# STM32F4_MCU.net
KiCad netlist of a schematic drawn in Altium Designer
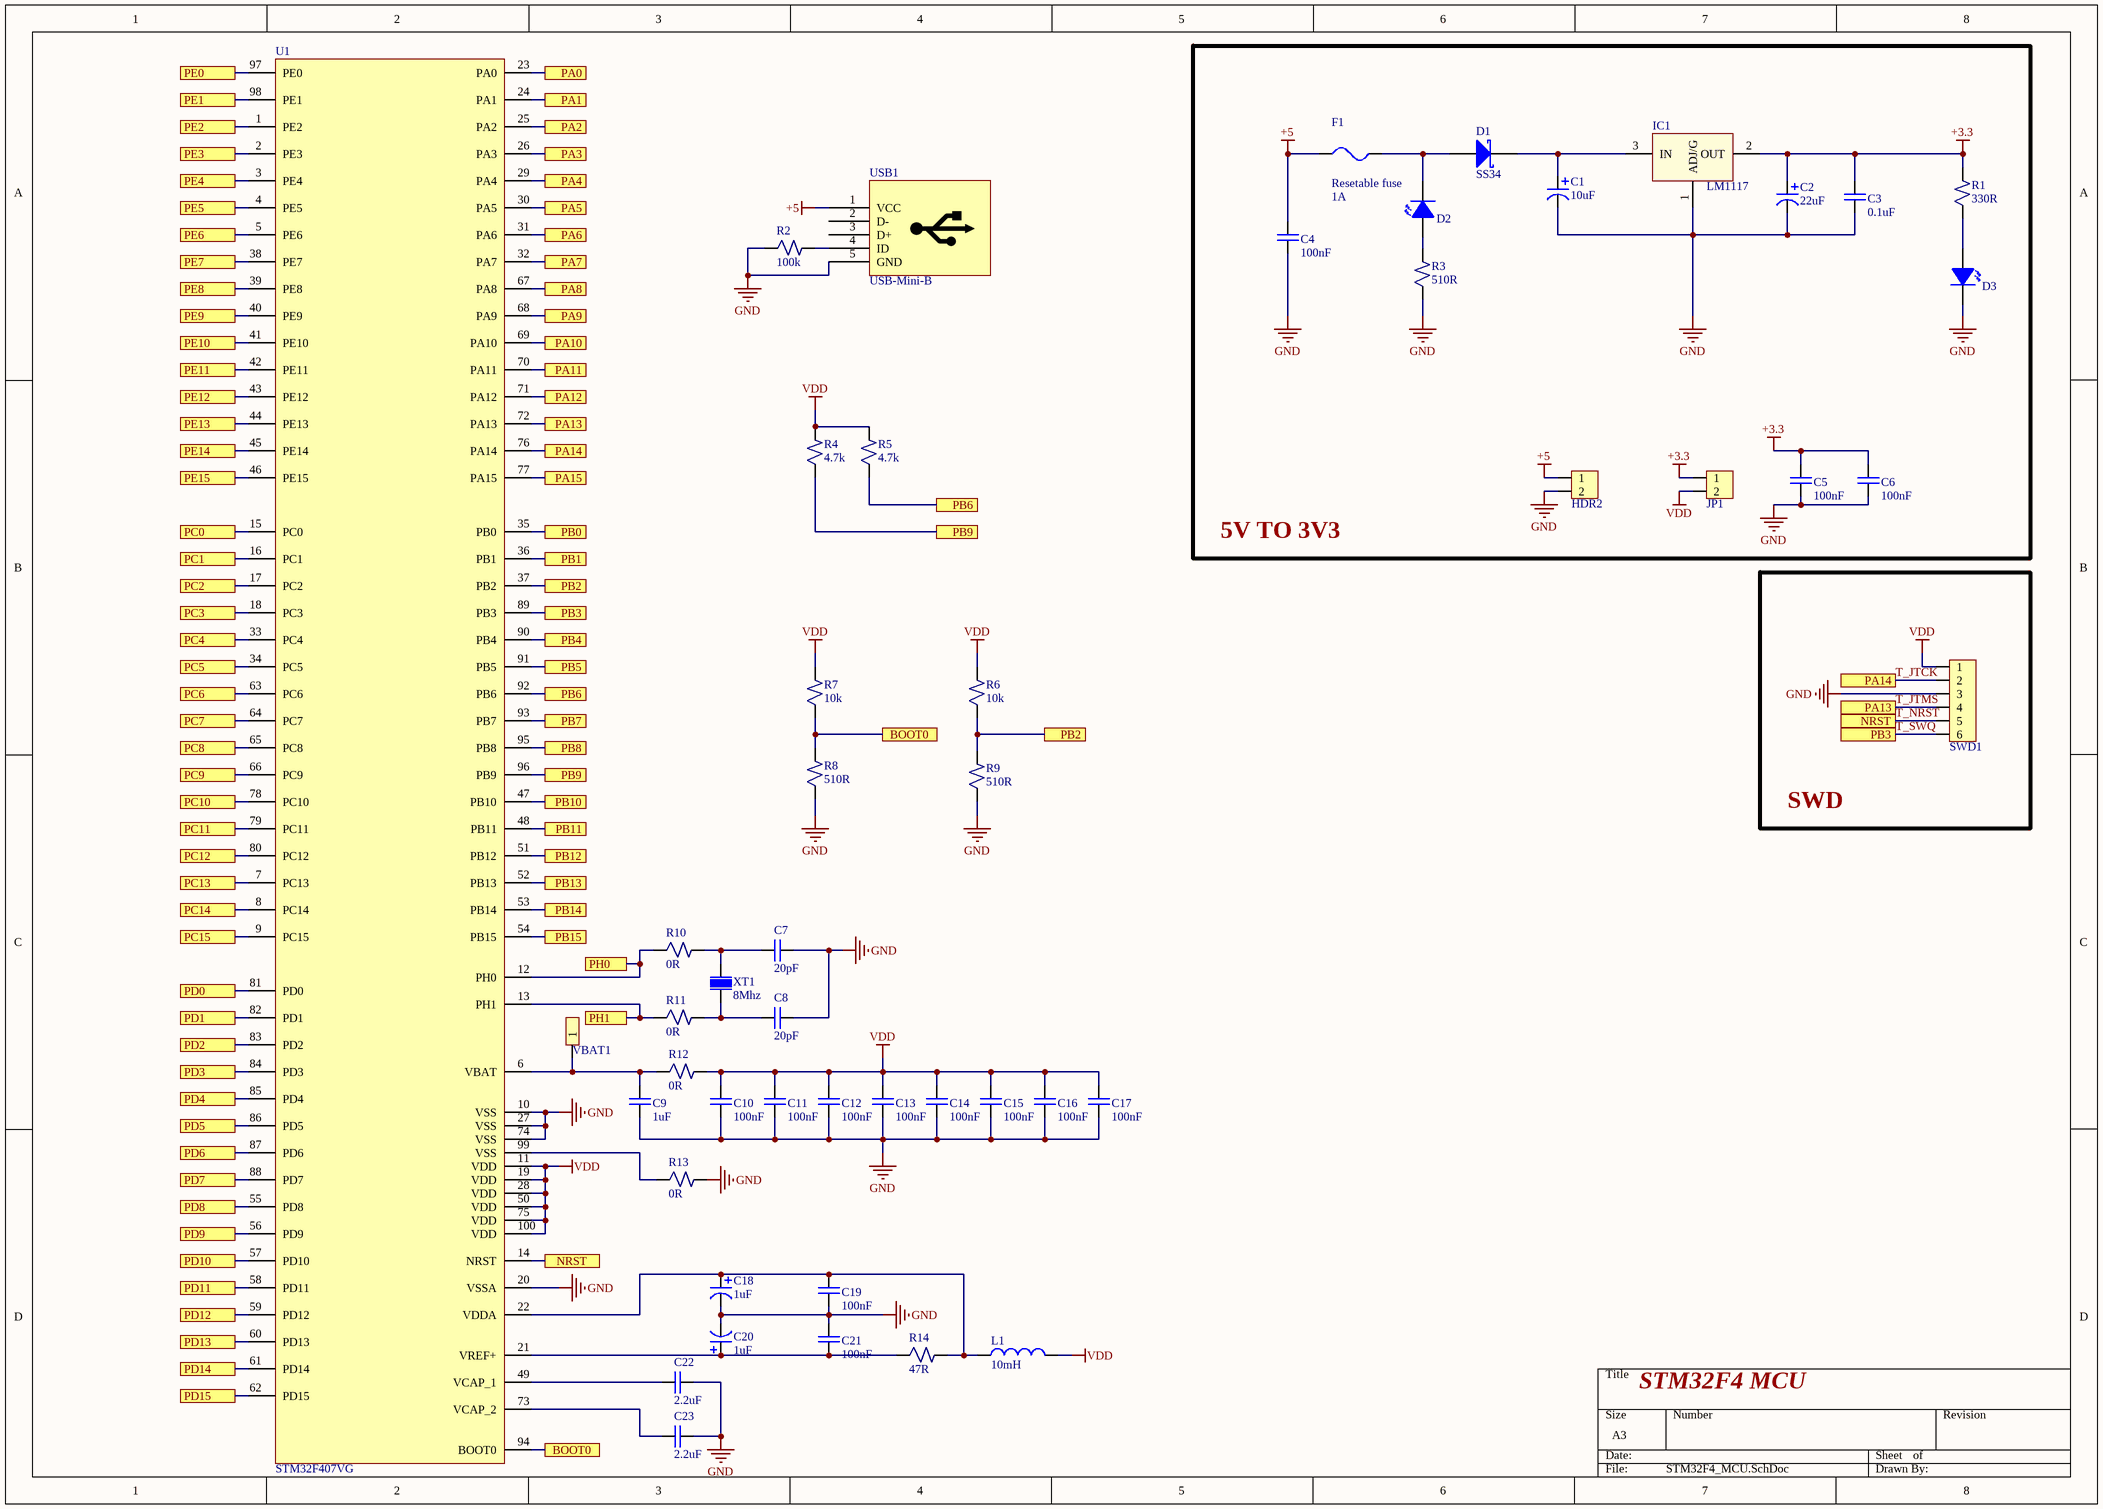
[diagram p0: STM32F4_MCU.SchDoc]

(export (version "E")
  (design (tool "Eeschema 10.0.6"))
  (components
    (comp (ref "C1")
      (value "10uF")
      (footprint "C3216-Tantalum")
      (description "Polarized Capacitor")
      (fields (field (name "Comment") "Cap Tantalum"))
      (libsource (lib "STM32F4_Board") (part "Cap Pol_2"))
    )
    (comp (ref "C2")
      (value "22uF")
      (footprint "C3216-Tantalum")
      (description "Polarized Capacitor")
      (fields (field (name "Comment") "Cap Pol"))
      (libsource (lib "STM32F4_Board") (part "Cap Pol_1"))
    )
    (comp (ref "C3")
      (value "0.1uF")
      (footprint "C0805")
      (description "Non-Polarized Capacitor")
      (fields (field (name "Comment") "Cap Non-Pol"))
      (libsource (lib "STM32F4_Board") (part "Cap Non-Pol_4"))
    )
    (comp (ref "C4")
      (value "100nF")
      (footprint "C0805")
      (description "Non-Polarized Capacitor")
      (fields (field (name "Comment") "Cap Non-Pol"))
      (libsource (lib "STM32F4_Board") (part "Cap Non-Pol"))
    )
    (comp (ref "C5")
      (value "100nF")
      (footprint "C0805")
      (description "Non-Polarized Capacitor")
      (fields (field (name "Comment") "Cap Non-Pol"))
      (libsource (lib "STM32F4_Board") (part "Cap Non-Pol"))
    )
    (comp (ref "C6")
      (value "100nF")
      (footprint "C0805")
      (description "Non-Polarized Capacitor")
      (fields (field (name "Comment") "Cap Non-Pol"))
      (libsource (lib "STM32F4_Board") (part "Cap Non-Pol"))
    )
    (comp (ref "C7")
      (value "20pF")
      (footprint "C0805")
      (description "Non-Polarized Capacitor")
      (fields (field (name "Comment") "Cap Non-Pol"))
      (libsource (lib "STM32F4_Board") (part "Cap Non-Pol_3"))
    )
    (comp (ref "C8")
      (value "20pF")
      (footprint "C0805")
      (description "Non-Polarized Capacitor")
      (fields (field (name "Comment") "Cap Non-Pol"))
      (libsource (lib "STM32F4_Board") (part "Cap Non-Pol_3"))
    )
    (comp (ref "C9")
      (value "1uF")
      (footprint "C0805")
      (description "Non-Polarized Capacitor")
      (fields (field (name "Comment") "Cap Non-Pol"))
      (libsource (lib "STM32F4_Board") (part "Cap Non-Pol_1"))
    )
    (comp (ref "C10")
      (value "100nF")
      (footprint "C0805")
      (description "Non-Polarized Capacitor")
      (fields (field (name "Comment") "Cap Non-Pol"))
      (libsource (lib "STM32F4_Board") (part "Cap Non-Pol"))
    )
    (comp (ref "C11")
      (value "100nF")
      (footprint "C0805")
      (description "Non-Polarized Capacitor")
      (fields (field (name "Comment") "Cap Non-Pol"))
      (libsource (lib "STM32F4_Board") (part "Cap Non-Pol"))
    )
    (comp (ref "C12")
      (value "100nF")
      (footprint "C0805")
      (description "Non-Polarized Capacitor")
      (fields (field (name "Comment") "Cap Non-Pol"))
      (libsource (lib "STM32F4_Board") (part "Cap Non-Pol"))
    )
    (comp (ref "C13")
      (value "100nF")
      (footprint "C0805")
      (description "Non-Polarized Capacitor")
      (fields (field (name "Comment") "Cap Non-Pol"))
      (libsource (lib "STM32F4_Board") (part "Cap Non-Pol"))
    )
    (comp (ref "C14")
      (value "100nF")
      (footprint "C0805")
      (description "Non-Polarized Capacitor")
      (fields (field (name "Comment") "Cap Non-Pol"))
      (libsource (lib "STM32F4_Board") (part "Cap Non-Pol"))
    )
    (comp (ref "C15")
      (value "100nF")
      (footprint "C0805")
      (description "Non-Polarized Capacitor")
      (fields (field (name "Comment") "Cap Non-Pol"))
      (libsource (lib "STM32F4_Board") (part "Cap Non-Pol"))
    )
    (comp (ref "C16")
      (value "100nF")
      (footprint "C0805")
      (description "Non-Polarized Capacitor")
      (fields (field (name "Comment") "Cap Non-Pol"))
      (libsource (lib "STM32F4_Board") (part "Cap Non-Pol"))
    )
    (comp (ref "C17")
      (value "100nF")
      (footprint "C0805")
      (description "Non-Polarized Capacitor")
      (fields (field (name "Comment") "Cap Non-Pol"))
      (libsource (lib "STM32F4_Board") (part "Cap Non-Pol"))
    )
    (comp (ref "C18")
      (value "1uF")
      (footprint "C3216-Tantalum")
      (description "Polarized Capacitor")
      (fields (field (name "Comment") "Cap Pol"))
      (libsource (lib "STM32F4_Board") (part "Cap Pol"))
    )
    (comp (ref "C19")
      (value "100nF")
      (footprint "C0805")
      (description "Non-Polarized Capacitor")
      (fields (field (name "Comment") "Cap Non-Pol"))
      (libsource (lib "STM32F4_Board") (part "Cap Non-Pol"))
    )
    (comp (ref "C20")
      (value "1uF")
      (footprint "C3216-Tantalum")
      (description "Polarized Capacitor")
      (fields (field (name "Comment") "Cap Pol"))
      (libsource (lib "STM32F4_Board") (part "Cap Pol"))
    )
    (comp (ref "C21")
      (value "100nF")
      (footprint "C0805")
      (description "Non-Polarized Capacitor")
      (fields (field (name "Comment") "Cap Non-Pol"))
      (libsource (lib "STM32F4_Board") (part "Cap Non-Pol"))
    )
    (comp (ref "C22")
      (value "2.2uF")
      (footprint "C0805")
      (description "Non-Polarized Capacitor")
      (fields (field (name "Comment") "Cap Non-Pol"))
      (libsource (lib "STM32F4_Board") (part "Cap Non-Pol_2"))
    )
    (comp (ref "C23")
      (value "2.2uF")
      (footprint "C0805")
      (description "Non-Polarized Capacitor")
      (fields (field (name "Comment") "Cap Non-Pol"))
      (libsource (lib "STM32F4_Board") (part "Cap Non-Pol_2"))
    )
    (comp (ref "D1")
      (value "SS34")
      (footprint "SMA")
      (description "Schottky Diode")
      (fields (field (name "PUBLISHER") "Altium Limited"))
      (libsource (lib "STM32F4_Board") (part "Diode Schottky"))
    )
    (comp (ref "D2") (value "LED") (footprint "LED0805") (libsource (lib "STM32F4_Board") (part "LED")))
    (comp (ref "D3") (value "LED") (footprint "LED0805") (libsource (lib "STM32F4_Board") (part "LED")))
    (comp (ref "F1")
      (value "Resetable fuse")
      (footprint "FUSE SMD")
      (description "Fuse")
      (fields (field (name "MAXCURRENT") "1A"))
      (libsource (lib "STM32F4_Board") (part "Fuse"))
    )
    (comp (ref "HDR2")
      (value "Header-2")
      (footprint "Header-2")
      (description "Header 2 pins")
      (libsource (lib "STM32F4_Board") (part "Header-2"))
    )
    (comp (ref "IC1")
      (value "LM1117")
      (footprint "SOT-223/SC-73")
      (description "Available in 1.8V, 2.5V, 2.85V, 3.3V, 5V, and  Adjustable Versions")
      (libsource (lib "STM32F4_Board") (part "LM1117"))
    )
    (comp (ref "JP1")
      (value "Header-2")
      (footprint "Header-2")
      (description "Header 2 pins")
      (libsource (lib "STM32F4_Board") (part "Header-2"))
    )
    (comp (ref "L1")
      (value "10mH")
      (footprint "R0805")
      (description "Inductor")
      (libsource (lib "STM32F4_Board") (part "Inductor"))
    )
    (comp (ref "R1")
      (value "330R")
      (footprint "R0805")
      (description "Resistor")
      (libsource (lib "STM32F4_Board") (part "Resistor_5"))
    )
    (comp (ref "R2")
      (value "100k")
      (footprint "R0805")
      (description "Resistor")
      (libsource (lib "STM32F4_Board") (part "Resistor_6"))
    )
    (comp (ref "R3")
      (value "510R")
      (footprint "R0805")
      (description "Resistor")
      (libsource (lib "STM32F4_Board") (part "Resistor_3"))
    )
    (comp (ref "R4")
      (value "4.7k")
      (footprint "R0805")
      (description "Resistor")
      (libsource (lib "STM32F4_Board") (part "Resistor_4"))
    )
    (comp (ref "R5")
      (value "4.7k")
      (footprint "R0805")
      (description "Resistor")
      (libsource (lib "STM32F4_Board") (part "Resistor_4"))
    )
    (comp (ref "R6")
      (value "10k")
      (footprint "R0805")
      (description "Resistor")
      (libsource (lib "STM32F4_Board") (part "Resistor_2"))
    )
    (comp (ref "R7")
      (value "10k")
      (footprint "R0805")
      (description "Resistor")
      (libsource (lib "STM32F4_Board") (part "Resistor_2"))
    )
    (comp (ref "R8")
      (value "510R")
      (footprint "R0805")
      (description "Resistor")
      (libsource (lib "STM32F4_Board") (part "Resistor_3"))
    )
    (comp (ref "R9")
      (value "510R")
      (footprint "R0805")
      (description "Resistor")
      (libsource (lib "STM32F4_Board") (part "Resistor_3"))
    )
    (comp (ref "R10")
      (value "0R")
      (footprint "R0805")
      (description "Resistor")
      (libsource (lib "STM32F4_Board") (part "Resistor_1"))
    )
    (comp (ref "R11")
      (value "0R")
      (footprint "R0805")
      (description "Resistor")
      (libsource (lib "STM32F4_Board") (part "Resistor_1"))
    )
    (comp (ref "R12")
      (value "0R")
      (footprint "R0805")
      (description "Resistor")
      (libsource (lib "STM32F4_Board") (part "Resistor_1"))
    )
    (comp (ref "R13")
      (value "0R")
      (footprint "R0805")
      (description "Resistor")
      (libsource (lib "STM32F4_Board") (part "Resistor_1"))
    )
    (comp (ref "R14")
      (value "47R")
      (footprint "R0805")
      (description "Resistor")
      (libsource (lib "STM32F4_Board") (part "Resistor"))
    )
    (comp (ref "SWD1")
      (value "Header-6")
      (footprint "Header-6")
      (description "Header 6 pins")
      (libsource (lib "STM32F4_Board") (part "Header-6"))
    )
    (comp (ref "U1")
      (value "STM32F407VG")
      (footprint "LQFP100")
      (libsource (lib "STM32F4_Board") (part "STM32F407VG"))
    )
    (comp (ref "USB1")
      (value "USB-Mini-B")
      (footprint "USB_B_MINI_SMD")
      (libsource (lib "STM32F4_Board") (part "USB-Mini"))
    )
    (comp (ref "VBAT1")
      (value "Header-1")
      (footprint "Header-1")
      (description "Header 1 pin")
      (libsource (lib "STM32F4_Board") (part "Header-1"))
    )
    (comp (ref "XT1")
      (value "XTAL")
      (footprint "XT2")
      (description "Crystal")
      (fields (field (name "FREQUENCY") "8Mhz"))
      (libsource (lib "STM32F4_Board") (part "XTAL"))
    )
  )
  (nets
    (net (code "1") (name "+3.3") (class "Default")
      (node (ref "C2") (pin "1") (pinfunction "1_1") (pintype "passive"))
      (node (ref "C3") (pin "2") (pinfunction "2_2") (pintype "passive"))
      (node (ref "C5") (pin "2") (pinfunction "2_2") (pintype "passive"))
      (node (ref "C6") (pin "2") (pinfunction "2_2") (pintype "passive"))
      (node (ref "IC1") (pin "2") (pinfunction "OUT_2") (pintype "passive"))
      (node (ref "JP1") (pin "1") (pinfunction "1_1") (pintype "passive"))
      (node (ref "R1") (pin "2") (pintype "passive"))
    )
    (net (code "2") (name "+5") (class "Default")
      (node (ref "C4") (pin "2") (pinfunction "2_2") (pintype "passive"))
      (node (ref "F1") (pin "1") (pinfunction "1_1") (pintype "passive"))
      (node (ref "HDR2") (pin "1") (pinfunction "1_1") (pintype "passive"))
      (node (ref "USB1") (pin "1") (pinfunction "VCC_1") (pintype "passive"))
    )
    (net (code "3") (name "/BOOT0") (class "Default")
      (node (ref "R7") (pin "1") (pintype "passive"))
      (node (ref "R8") (pin "2") (pintype "passive"))
      (node (ref "U1") (pin "94") (pinfunction "BOOT0_94") (pintype "passive"))
    )
    (net (code "4") (name "/PA0") (class "Default")
      (node (ref "U1") (pin "23") (pinfunction "PA0_23") (pintype "passive"))
    )
    (net (code "5") (name "/PA1") (class "Default")
      (node (ref "U1") (pin "24") (pinfunction "PA1_24") (pintype "passive"))
    )
    (net (code "6") (name "/PA2") (class "Default")
      (node (ref "U1") (pin "25") (pinfunction "PA2_25") (pintype "passive"))
    )
    (net (code "7") (name "/PA3") (class "Default")
      (node (ref "U1") (pin "26") (pinfunction "PA3_26") (pintype "passive"))
    )
    (net (code "8") (name "/PA4") (class "Default")
      (node (ref "U1") (pin "29") (pinfunction "PA4_29") (pintype "passive"))
    )
    (net (code "9") (name "/PA5") (class "Default")
      (node (ref "U1") (pin "30") (pinfunction "PA5_30") (pintype "passive"))
    )
    (net (code "10") (name "/PA6") (class "Default")
      (node (ref "U1") (pin "31") (pinfunction "PA6_31") (pintype "passive"))
    )
    (net (code "11") (name "/PA7") (class "Default")
      (node (ref "U1") (pin "32") (pinfunction "PA7_32") (pintype "passive"))
    )
    (net (code "12") (name "/PA8") (class "Default")
      (node (ref "U1") (pin "67") (pinfunction "PA8_67") (pintype "passive"))
    )
    (net (code "13") (name "/PA9") (class "Default")
      (node (ref "U1") (pin "68") (pinfunction "PA9_68") (pintype "passive"))
    )
    (net (code "14") (name "/PA10") (class "Default")
      (node (ref "U1") (pin "69") (pinfunction "PA10_69") (pintype "passive"))
    )
    (net (code "15") (name "/PA11") (class "Default")
      (node (ref "U1") (pin "70") (pinfunction "PA11_70") (pintype "passive"))
    )
    (net (code "16") (name "/PA12") (class "Default")
      (node (ref "U1") (pin "71") (pinfunction "PA12_71") (pintype "passive"))
    )
    (net (code "17") (name "/PA15") (class "Default")
      (node (ref "U1") (pin "77") (pinfunction "PA15_77") (pintype "passive"))
    )
    (net (code "18") (name "/PB0") (class "Default")
      (node (ref "U1") (pin "35") (pinfunction "PB0_35") (pintype "passive"))
    )
    (net (code "19") (name "/PB1") (class "Default")
      (node (ref "U1") (pin "36") (pinfunction "PB1_36") (pintype "passive"))
    )
    (net (code "20") (name "/PB2") (class "Default")
      (node (ref "R6") (pin "1") (pintype "passive"))
      (node (ref "R9") (pin "2") (pintype "passive"))
      (node (ref "U1") (pin "37") (pinfunction "PB2_37") (pintype "passive"))
    )
    (net (code "21") (name "/PB4") (class "Default")
      (node (ref "U1") (pin "90") (pinfunction "PB4_90") (pintype "passive"))
    )
    (net (code "22") (name "/PB5") (class "Default")
      (node (ref "U1") (pin "91") (pinfunction "PB5_91") (pintype "passive"))
    )
    (net (code "23") (name "/PB6") (class "Default")
      (node (ref "R5") (pin "1") (pintype "passive"))
      (node (ref "U1") (pin "92") (pinfunction "PB6_92") (pintype "passive"))
    )
    (net (code "24") (name "/PB7") (class "Default")
      (node (ref "U1") (pin "93") (pinfunction "PB7_93") (pintype "passive"))
    )
    (net (code "25") (name "/PB8") (class "Default")
      (node (ref "U1") (pin "95") (pinfunction "PB8_95") (pintype "passive"))
    )
    (net (code "26") (name "/PB9") (class "Default")
      (node (ref "R4") (pin "1") (pintype "passive"))
      (node (ref "U1") (pin "96") (pinfunction "PB9_96") (pintype "passive"))
    )
    (net (code "27") (name "/PB10") (class "Default")
      (node (ref "U1") (pin "47") (pinfunction "PB10_47") (pintype "passive"))
    )
    (net (code "28") (name "/PB11") (class "Default")
      (node (ref "U1") (pin "48") (pinfunction "PB11_48") (pintype "passive"))
    )
    (net (code "29") (name "/PB12") (class "Default")
      (node (ref "U1") (pin "51") (pinfunction "PB12_51") (pintype "passive"))
    )
    (net (code "30") (name "/PB13") (class "Default")
      (node (ref "U1") (pin "52") (pinfunction "PB13_52") (pintype "passive"))
    )
    (net (code "31") (name "/PB14") (class "Default")
      (node (ref "U1") (pin "53") (pinfunction "PB14_53") (pintype "passive"))
    )
    (net (code "32") (name "/PB15") (class "Default")
      (node (ref "U1") (pin "54") (pinfunction "PB15_54") (pintype "passive"))
    )
    (net (code "33") (name "/PC0") (class "Default")
      (node (ref "U1") (pin "15") (pinfunction "PC0_15") (pintype "passive"))
    )
    (net (code "34") (name "/PC1") (class "Default")
      (node (ref "U1") (pin "16") (pinfunction "PC1_16") (pintype "passive"))
    )
    (net (code "35") (name "/PC2") (class "Default")
      (node (ref "U1") (pin "17") (pinfunction "PC2_17") (pintype "passive"))
    )
    (net (code "36") (name "/PC3") (class "Default")
      (node (ref "U1") (pin "18") (pinfunction "PC3_18") (pintype "passive"))
    )
    (net (code "37") (name "/PC4") (class "Default")
      (node (ref "U1") (pin "33") (pinfunction "PC4_33") (pintype "passive"))
    )
    (net (code "38") (name "/PC5") (class "Default")
      (node (ref "U1") (pin "34") (pinfunction "PC5_34") (pintype "passive"))
    )
    (net (code "39") (name "/PC6") (class "Default")
      (node (ref "U1") (pin "63") (pinfunction "PC6_63") (pintype "passive"))
    )
    (net (code "40") (name "/PC7") (class "Default")
      (node (ref "U1") (pin "64") (pinfunction "PC7_64") (pintype "passive"))
    )
    (net (code "41") (name "/PC8") (class "Default")
      (node (ref "U1") (pin "65") (pinfunction "PC8_65") (pintype "passive"))
    )
    (net (code "42") (name "/PC9") (class "Default")
      (node (ref "U1") (pin "66") (pinfunction "PC9_66") (pintype "passive"))
    )
    (net (code "43") (name "/PC10") (class "Default")
      (node (ref "U1") (pin "78") (pinfunction "PC10_78") (pintype "passive"))
    )
    (net (code "44") (name "/PC11") (class "Default")
      (node (ref "U1") (pin "79") (pinfunction "PC11_79") (pintype "passive"))
    )
    (net (code "45") (name "/PC12") (class "Default")
      (node (ref "U1") (pin "80") (pinfunction "PC12_80") (pintype "passive"))
    )
    (net (code "46") (name "/PC13") (class "Default")
      (node (ref "U1") (pin "7") (pinfunction "PC13_7") (pintype "passive"))
    )
    (net (code "47") (name "/PC14") (class "Default")
      (node (ref "U1") (pin "8") (pinfunction "PC14_8") (pintype "passive"))
    )
    (net (code "48") (name "/PC15") (class "Default")
      (node (ref "U1") (pin "9") (pinfunction "PC15_9") (pintype "passive"))
    )
    (net (code "49") (name "/PD0") (class "Default")
      (node (ref "U1") (pin "81") (pinfunction "PD0_81") (pintype "passive"))
    )
    (net (code "50") (name "/PD1") (class "Default")
      (node (ref "U1") (pin "82") (pinfunction "PD1_82") (pintype "passive"))
    )
    (net (code "51") (name "/PD2") (class "Default")
      (node (ref "U1") (pin "83") (pinfunction "PD2_83") (pintype "passive"))
    )
    (net (code "52") (name "/PD3") (class "Default")
      (node (ref "U1") (pin "84") (pinfunction "PD3_84") (pintype "passive"))
    )
    (net (code "53") (name "/PD4") (class "Default")
      (node (ref "U1") (pin "85") (pinfunction "PD4_85") (pintype "passive"))
    )
    (net (code "54") (name "/PD5") (class "Default")
      (node (ref "U1") (pin "86") (pinfunction "PD5_86") (pintype "passive"))
    )
    (net (code "55") (name "/PD6") (class "Default")
      (node (ref "U1") (pin "87") (pinfunction "PD6_87") (pintype "passive"))
    )
    (net (code "56") (name "/PD7") (class "Default")
      (node (ref "U1") (pin "88") (pinfunction "PD7_88") (pintype "passive"))
    )
    (net (code "57") (name "/PD8") (class "Default")
      (node (ref "U1") (pin "55") (pinfunction "PD8_55") (pintype "passive"))
    )
    (net (code "58") (name "/PD9") (class "Default")
      (node (ref "U1") (pin "56") (pinfunction "PD9_56") (pintype "passive"))
    )
    (net (code "59") (name "/PD10") (class "Default")
      (node (ref "U1") (pin "57") (pinfunction "PD10_57") (pintype "passive"))
    )
    (net (code "60") (name "/PD11") (class "Default")
      (node (ref "U1") (pin "58") (pinfunction "PD11_58") (pintype "passive"))
    )
    (net (code "61") (name "/PD12") (class "Default")
      (node (ref "U1") (pin "59") (pinfunction "PD12_59") (pintype "passive"))
    )
    (net (code "62") (name "/PD13") (class "Default")
      (node (ref "U1") (pin "60") (pinfunction "PD13_60") (pintype "passive"))
    )
    (net (code "63") (name "/PD14") (class "Default")
      (node (ref "U1") (pin "61") (pinfunction "PD14_61") (pintype "passive"))
    )
    (net (code "64") (name "/PD15") (class "Default")
      (node (ref "U1") (pin "62") (pinfunction "PD15_62") (pintype "passive"))
    )
    (net (code "65") (name "/PE0") (class "Default")
      (node (ref "U1") (pin "97") (pinfunction "PE0_97") (pintype "passive"))
    )
    (net (code "66") (name "/PE1") (class "Default")
      (node (ref "U1") (pin "98") (pinfunction "PE1_98") (pintype "passive"))
    )
    (net (code "67") (name "/PE2") (class "Default")
      (node (ref "U1") (pin "1") (pinfunction "PE2_1") (pintype "passive"))
    )
    (net (code "68") (name "/PE3") (class "Default")
      (node (ref "U1") (pin "2") (pinfunction "PE3_2") (pintype "passive"))
    )
    (net (code "69") (name "/PE4") (class "Default")
      (node (ref "U1") (pin "3") (pinfunction "PE4_3") (pintype "passive"))
    )
    (net (code "70") (name "/PE5") (class "Default")
      (node (ref "U1") (pin "4") (pinfunction "PE5_4") (pintype "passive"))
    )
    (net (code "71") (name "/PE6") (class "Default")
      (node (ref "U1") (pin "5") (pinfunction "PE6_5") (pintype "passive"))
    )
    (net (code "72") (name "/PE7") (class "Default")
      (node (ref "U1") (pin "38") (pinfunction "PE7_38") (pintype "passive"))
    )
    (net (code "73") (name "/PE8") (class "Default")
      (node (ref "U1") (pin "39") (pinfunction "PE8_39") (pintype "passive"))
    )
    (net (code "74") (name "/PE9") (class "Default")
      (node (ref "U1") (pin "40") (pinfunction "PE9_40") (pintype "passive"))
    )
    (net (code "75") (name "/PE10") (class "Default")
      (node (ref "U1") (pin "41") (pinfunction "PE10_41") (pintype "passive"))
    )
    (net (code "76") (name "/PE11") (class "Default")
      (node (ref "U1") (pin "42") (pinfunction "PE11_42") (pintype "passive"))
    )
    (net (code "77") (name "/PE12") (class "Default")
      (node (ref "U1") (pin "43") (pinfunction "PE12_43") (pintype "passive"))
    )
    (net (code "78") (name "/PE13") (class "Default")
      (node (ref "U1") (pin "44") (pinfunction "PE13_44") (pintype "passive"))
    )
    (net (code "79") (name "/PE14") (class "Default")
      (node (ref "U1") (pin "45") (pinfunction "PE14_45") (pintype "passive"))
    )
    (net (code "80") (name "/PE15") (class "Default")
      (node (ref "U1") (pin "46") (pinfunction "PE15_46") (pintype "passive"))
    )
    (net (code "81") (name "/PH0") (class "Default")
      (node (ref "R10") (pin "1") (pintype "passive"))
      (node (ref "U1") (pin "12") (pinfunction "PH0_12") (pintype "passive"))
    )
    (net (code "82") (name "/PH1") (class "Default")
      (node (ref "R11") (pin "1") (pintype "passive"))
      (node (ref "U1") (pin "13") (pinfunction "PH1_13") (pintype "passive"))
    )
    (net (code "83") (name "/T_JTCK") (class "Default")
      (node (ref "SWD1") (pin "2") (pinfunction "2_2") (pintype "passive"))
      (node (ref "U1") (pin "76") (pinfunction "PA14_76") (pintype "passive"))
    )
    (net (code "84") (name "/T_JTMS") (class "Default")
      (node (ref "SWD1") (pin "4") (pinfunction "4_4") (pintype "passive"))
      (node (ref "U1") (pin "72") (pinfunction "PA13_72") (pintype "passive"))
    )
    (net (code "85") (name "/T_NRST") (class "Default")
      (node (ref "SWD1") (pin "5") (pinfunction "5_5") (pintype "passive"))
      (node (ref "U1") (pin "14") (pinfunction "NRST_14") (pintype "passive"))
    )
    (net (code "86") (name "/T_SWQ") (class "Default")
      (node (ref "SWD1") (pin "6") (pinfunction "6_6") (pintype "passive"))
      (node (ref "U1") (pin "89") (pinfunction "PB3_89") (pintype "passive"))
    )
    (net (code "87") (name "GND") (class "Default")
      (node (ref "C1") (pin "2") (pinfunction "2_2") (pintype "passive"))
      (node (ref "C10") (pin "2") (pinfunction "2_2") (pintype "passive"))
      (node (ref "C11") (pin "2") (pinfunction "2_2") (pintype "passive"))
      (node (ref "C12") (pin "2") (pinfunction "2_2") (pintype "passive"))
      (node (ref "C13") (pin "2") (pinfunction "2_2") (pintype "passive"))
      (node (ref "C14") (pin "2") (pinfunction "2_2") (pintype "passive"))
      (node (ref "C15") (pin "2") (pinfunction "2_2") (pintype "passive"))
      (node (ref "C16") (pin "2") (pinfunction "2_2") (pintype "passive"))
      (node (ref "C17") (pin "2") (pinfunction "2_2") (pintype "passive"))
      (node (ref "C18") (pin "2") (pinfunction "2_2") (pintype "passive"))
      (node (ref "C19") (pin "1") (pinfunction "1_1") (pintype "passive"))
      (node (ref "C2") (pin "2") (pinfunction "2_2") (pintype "passive"))
      (node (ref "C20") (pin "2") (pinfunction "2_2") (pintype "passive"))
      (node (ref "C21") (pin "1") (pinfunction "1_1") (pintype "passive"))
      (node (ref "C22") (pin "2") (pinfunction "2_2") (pintype "passive"))
      (node (ref "C23") (pin "2") (pinfunction "2_2") (pintype "passive"))
      (node (ref "C3") (pin "1") (pinfunction "1_1") (pintype "passive"))
      (node (ref "C4") (pin "1") (pinfunction "1_1") (pintype "passive"))
      (node (ref "C5") (pin "1") (pinfunction "1_1") (pintype "passive"))
      (node (ref "C6") (pin "1") (pinfunction "1_1") (pintype "passive"))
      (node (ref "C7") (pin "2") (pinfunction "2_2") (pintype "passive"))
      (node (ref "C8") (pin "2") (pinfunction "2_2") (pintype "passive"))
      (node (ref "C9") (pin "2") (pinfunction "2_2") (pintype "passive"))
      (node (ref "D3") (pin "2") (pinfunction "2_2") (pintype "passive"))
      (node (ref "HDR2") (pin "2") (pinfunction "2_2") (pintype "passive"))
      (node (ref "IC1") (pin "1") (pinfunction "ADJ/G_1") (pintype "passive"))
      (node (ref "R13") (pin "2") (pintype "passive"))
      (node (ref "R2") (pin "1") (pintype "passive"))
      (node (ref "R3") (pin "1") (pintype "passive"))
      (node (ref "R8") (pin "1") (pintype "passive"))
      (node (ref "R9") (pin "1") (pintype "passive"))
      (node (ref "SWD1") (pin "3") (pinfunction "3_3") (pintype "passive"))
      (node (ref "U1") (pin "10") (pinfunction "VSS_10") (pintype "passive"))
      (node (ref "U1") (pin "20") (pinfunction "VSSA_20") (pintype "passive"))
      (node (ref "U1") (pin "27") (pinfunction "VSS_27") (pintype "passive"))
      (node (ref "U1") (pin "74") (pinfunction "VSS_74") (pintype "passive"))
      (node (ref "USB1") (pin "5") (pinfunction "GND_5") (pintype "passive"))
    )
    (net (code "88") (name "Net-(C7-Pad1)") (class "Default")
      (node (ref "C7") (pin "1") (pinfunction "1_1") (pintype "passive"))
      (node (ref "R10") (pin "2") (pintype "passive"))
      (node (ref "XT1") (pin "2") (pinfunction "2_2") (pintype "passive"))
    )
    (net (code "89") (name "Net-(C8-Pad1)") (class "Default")
      (node (ref "C8") (pin "1") (pinfunction "1_1") (pintype "passive"))
      (node (ref "R11") (pin "2") (pintype "passive"))
      (node (ref "XT1") (pin "1") (pinfunction "1_1") (pintype "passive"))
    )
    (net (code "90") (name "Net-(D1-A)") (class "Default")
      (node (ref "D1") (pin "1") (pinfunction "A_1") (pintype "passive"))
      (node (ref "D2") (pin "2") (pinfunction "2_2") (pintype "passive"))
      (node (ref "F1") (pin "2") (pinfunction "2_2") (pintype "passive"))
    )
    (net (code "91") (name "Net-(D1-K)") (class "Default")
      (node (ref "C1") (pin "1") (pinfunction "1_1") (pintype "passive"))
      (node (ref "D1") (pin "2") (pinfunction "K_2") (pintype "passive"))
      (node (ref "IC1") (pin "3") (pinfunction "IN_3") (pintype "passive"))
    )
    (net (code "92") (name "Net-(D2-Pad1)") (class "Default")
      (node (ref "D2") (pin "1") (pinfunction "1_1") (pintype "passive"))
      (node (ref "R3") (pin "2") (pintype "passive"))
    )
    (net (code "93") (name "Net-(D3-Pad1)") (class "Default")
      (node (ref "D3") (pin "1") (pinfunction "1_1") (pintype "passive"))
      (node (ref "R1") (pin "1") (pintype "passive"))
    )
    (net (code "94") (name "Net-(R13-Pad1)") (class "Default")
      (node (ref "R13") (pin "1") (pintype "passive"))
      (node (ref "U1") (pin "99") (pinfunction "VSS_99") (pintype "passive"))
    )
    (net (code "95") (name "Net-(U1-VBAT)") (class "Default")
      (node (ref "C9") (pin "1") (pinfunction "1_1") (pintype "passive"))
      (node (ref "R12") (pin "1") (pintype "passive"))
      (node (ref "U1") (pin "6") (pinfunction "VBAT_6") (pintype "passive"))
      (node (ref "VBAT1") (pin "1") (pinfunction "1_1") (pintype "passive"))
    )
    (net (code "96") (name "Net-(U1-VCAP_1)") (class "Default")
      (node (ref "C22") (pin "1") (pinfunction "1_1") (pintype "passive"))
      (node (ref "U1") (pin "49") (pinfunction "VCAP_1_49") (pintype "passive"))
    )
    (net (code "97") (name "Net-(U1-VCAP_2)") (class "Default")
      (node (ref "C23") (pin "1") (pinfunction "1_1") (pintype "passive"))
      (node (ref "U1") (pin "73") (pinfunction "VCAP_2_73") (pintype "passive"))
    )
    (net (code "98") (name "Net-(U1-VDDA)") (class "Default")
      (node (ref "C18") (pin "1") (pinfunction "1_1") (pintype "passive"))
      (node (ref "C19") (pin "2") (pinfunction "2_2") (pintype "passive"))
      (node (ref "L1") (pin "1") (pinfunction "1_1") (pintype "passive"))
      (node (ref "R14") (pin "2") (pintype "passive"))
      (node (ref "U1") (pin "22") (pinfunction "VDDA_22") (pintype "passive"))
    )
    (net (code "99") (name "Net-(U1-VREF+)") (class "Default")
      (node (ref "C20") (pin "1") (pinfunction "1_1") (pintype "passive"))
      (node (ref "C21") (pin "2") (pinfunction "2_2") (pintype "passive"))
      (node (ref "R14") (pin "1") (pintype "passive"))
      (node (ref "U1") (pin "21") (pinfunction "VREF+_21") (pintype "passive"))
    )
    (net (code "100") (name "Net-(USB1-ID)") (class "Default")
      (node (ref "R2") (pin "2") (pintype "passive"))
      (node (ref "USB1") (pin "4") (pinfunction "ID_4") (pintype "passive"))
    )
    (net (code "101") (name "VDD") (class "Default")
      (node (ref "C10") (pin "1") (pinfunction "1_1") (pintype "passive"))
      (node (ref "C11") (pin "1") (pinfunction "1_1") (pintype "passive"))
      (node (ref "C12") (pin "1") (pinfunction "1_1") (pintype "passive"))
      (node (ref "C13") (pin "1") (pinfunction "1_1") (pintype "passive"))
      (node (ref "C14") (pin "1") (pinfunction "1_1") (pintype "passive"))
      (node (ref "C15") (pin "1") (pinfunction "1_1") (pintype "passive"))
      (node (ref "C16") (pin "1") (pinfunction "1_1") (pintype "passive"))
      (node (ref "C17") (pin "1") (pinfunction "1_1") (pintype "passive"))
      (node (ref "JP1") (pin "2") (pinfunction "2_2") (pintype "passive"))
      (node (ref "L1") (pin "2") (pinfunction "2_2") (pintype "passive"))
      (node (ref "R12") (pin "2") (pintype "passive"))
      (node (ref "R4") (pin "2") (pintype "passive"))
      (node (ref "R5") (pin "2") (pintype "passive"))
      (node (ref "R6") (pin "2") (pintype "passive"))
      (node (ref "R7") (pin "2") (pintype "passive"))
      (node (ref "SWD1") (pin "1") (pinfunction "1_1") (pintype "passive"))
      (node (ref "U1") (pin "100") (pinfunction "VDD_100") (pintype "passive"))
      (node (ref "U1") (pin "11") (pinfunction "VDD_11") (pintype "passive"))
      (node (ref "U1") (pin "19") (pinfunction "VDD_19") (pintype "passive"))
      (node (ref "U1") (pin "28") (pinfunction "VDD_28") (pintype "passive"))
      (node (ref "U1") (pin "50") (pinfunction "VDD_50") (pintype "passive"))
      (node (ref "U1") (pin "75") (pinfunction "VDD_75") (pintype "passive"))
    )
    (net (code "102") (name "unconnected-(USB1-D+-Pad3)") (class "Default")
      (node (ref "USB1") (pin "3") (pinfunction "D+_3") (pintype "passive"))
    )
    (net (code "103") (name "unconnected-(USB1-D--Pad2)") (class "Default")
      (node (ref "USB1") (pin "2") (pinfunction "D-_2") (pintype "passive"))
    )
  )
)
